# CurrentCost.net
KiCad netlist of a schematic drawn in EAGLE
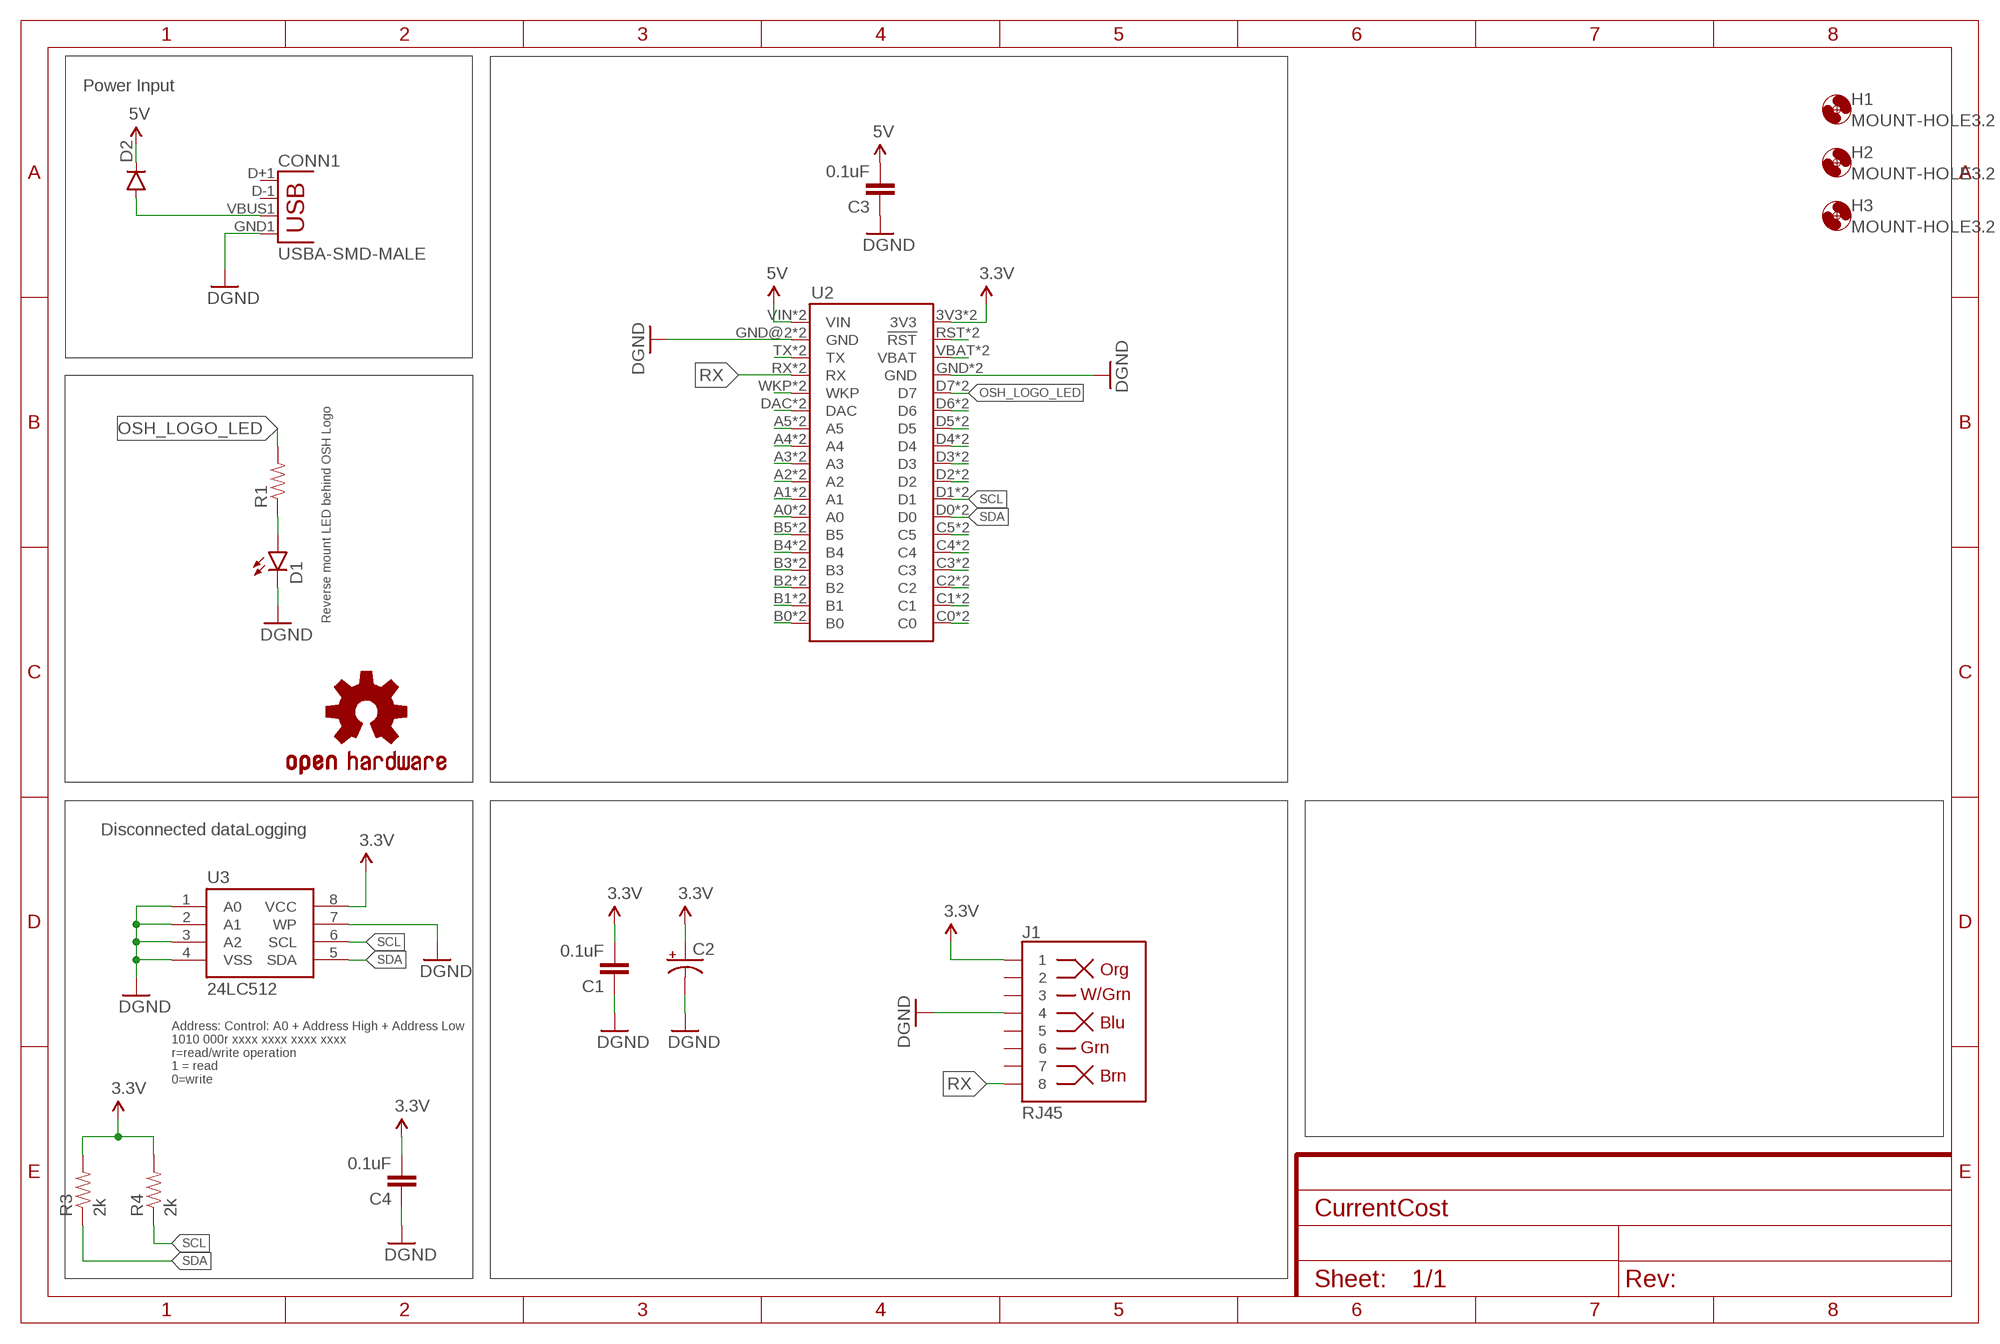
[diagram p0: schematic, sheet 1]

(export (version "E")
  (design (tool "Eeschema 10.0.6"))
  (components
    (comp (ref "C1")
      (value "0.1uF")
      (footprint "eagle-import:0805")
      (libsource (lib "eagle-import") (part "CAP0805"))
    )
    (comp (ref "C2")
      (value "CAP_POLPTH1")
      (footprint "eagle-import:CPOL-RADIAL-100UF-25V")
      (libsource (lib "eagle-import") (part "CAP_POLPTH1"))
    )
    (comp (ref "C3")
      (value "0.1uF")
      (footprint "eagle-import:0805")
      (libsource (lib "eagle-import") (part "CAP0805"))
    )
    (comp (ref "C4")
      (value "0.1uF")
      (footprint "eagle-import:0805")
      (libsource (lib "eagle-import") (part "CAP0805"))
    )
    (comp (ref "CONN1")
      (value "USBA-SMD-MALE")
      (footprint "eagle-import:USB-A-SMT-MALE")
      (libsource (lib "eagle-import") (part "USBA-SMD-MALE"))
    )
    (comp (ref "D1")
      (value "LED1206-BOTTOM")
      (footprint "eagle-import:LED-1206-BOTTOM")
      (libsource (lib "eagle-import") (part "LED1206-BOTTOM"))
    )
    (comp (ref "D2")
      (value "DIODESMA")
      (footprint "eagle-import:SMA-DIODE")
      (libsource (lib "eagle-import") (part "DIODESMA"))
    )
    (comp (ref "H1")
      (value "MOUNT-HOLE3.2")
      (footprint "eagle-import:3,2")
      (libsource (lib "eagle-import") (part "MOUNT-HOLE3.2"))
    )
    (comp (ref "H2")
      (value "MOUNT-HOLE3.2")
      (footprint "eagle-import:3,2")
      (libsource (lib "eagle-import") (part "MOUNT-HOLE3.2"))
    )
    (comp (ref "H3")
      (value "MOUNT-HOLE3.2")
      (footprint "eagle-import:3,2")
      (libsource (lib "eagle-import") (part "MOUNT-HOLE3.2"))
    )
    (comp (ref "J1")
      (value "RJ45")
      (footprint "eagle-import:RJ45-8")
      (libsource (lib "eagle-import") (part "RJ45-8PTH"))
    )
    (comp (ref "LOGO1")
      (value "OSHW-LOGOM")
      (footprint "eagle-import:OSHW-LOGO-M")
      (libsource (lib "eagle-import") (part "OSHW-LOGOM"))
    )
    (comp (ref "R1")
      (value "RESISTOR1206")
      (footprint "eagle-import:1206")
      (libsource (lib "eagle-import") (part "RESISTOR1206"))
    )
    (comp (ref "R3")
      (value "2k")
      (footprint "eagle-import:0805")
      (libsource (lib "eagle-import") (part "RESISTOR0805-RES"))
    )
    (comp (ref "R4")
      (value "2k")
      (footprint "eagle-import:0805")
      (libsource (lib "eagle-import") (part "RESISTOR0805-RES"))
    )
    (comp (ref "U2")
      (value "ELECTRONDUALNAMED")
      (footprint "eagle-import:ELECTRON_SIMPLE_SILK_NAMES_DUAL")
      (libsource (lib "eagle-import") (part "ELECTRONDUALNAMED"))
    )
    (comp (ref "U3")
      (value "24LC512")
      (footprint "eagle-import:SO08")
      (libsource (lib "eagle-import") (part "EEPROM-I2CSMD"))
    )
  )
  (nets
    (net (code "1") (name "3.3V") (class "Default")
      (node (ref "C1") (pin "2") (pinfunction "2_2") (pintype "passive"))
      (node (ref "C2") (pin "1") (pinfunction "+_1") (pintype "passive"))
      (node (ref "C4") (pin "2") (pinfunction "2_2") (pintype "passive"))
      (node (ref "J1") (pin "1") (pinfunction "1_1") (pintype "bidirectional"))
      (node (ref "R3") (pin "2") (pinfunction "2_2") (pintype "passive"))
      (node (ref "R4") (pin "2") (pinfunction "2_2") (pintype "passive"))
      (node (ref "U2") (pin "3V3") (pinfunction "3V3_3V3") (pintype "power_in"))
      (node (ref "U2") (pin "3V3_1") (pinfunction "3V3_3V3_1") (pintype "power_in"))
      (node (ref "U3") (pin "8") (pinfunction "VCC_8") (pintype "power_in"))
    )
    (net (code "2") (name "5V") (class "Default")
      (node (ref "C3") (pin "2") (pinfunction "2_2") (pintype "passive"))
      (node (ref "D2") (pin "C") (pinfunction "C_C") (pintype "passive"))
      (node (ref "U2") (pin "VIN") (pinfunction "VIN_VIN") (pintype "power_in"))
      (node (ref "U2") (pin "VIN_1B") (pinfunction "VIN_VIN_1B") (pintype "power_in"))
    )
    (net (code "3") (name "DGND") (class "Default")
      (node (ref "C1") (pin "1") (pinfunction "1_1") (pintype "passive"))
      (node (ref "C2") (pin "2") (pinfunction "-_2") (pintype "passive"))
      (node (ref "C3") (pin "1") (pinfunction "1_1") (pintype "passive"))
      (node (ref "C4") (pin "1") (pinfunction "1_1") (pintype "passive"))
      (node (ref "CONN1") (pin "GND1") (pinfunction "GND_GND1") (pintype "bidirectional"))
      (node (ref "D1") (pin "C") (pinfunction "C_C") (pintype "passive"))
      (node (ref "J1") (pin "4") (pinfunction "4_4") (pintype "bidirectional"))
      (node (ref "U2") (pin "GND") (pinfunction "GND_GND") (pintype "power_in"))
      (node (ref "U2") (pin "GND@2") (pinfunction "GND_GND@2") (pintype "power_in"))
      (node (ref "U2") (pin "GND_1") (pinfunction "GND_GND_1") (pintype "power_in"))
      (node (ref "U2") (pin "GND_1B") (pinfunction "GND_GND_1B") (pintype "power_in"))
      (node (ref "U3") (pin "1") (pinfunction "A0_1") (pintype "bidirectional"))
      (node (ref "U3") (pin "2") (pinfunction "A1_2") (pintype "bidirectional"))
      (node (ref "U3") (pin "3") (pinfunction "A2_3") (pintype "bidirectional"))
      (node (ref "U3") (pin "4") (pinfunction "VSS_4") (pintype "power_in"))
      (node (ref "U3") (pin "7") (pinfunction "WP_7") (pintype "bidirectional"))
    )
    (net (code "4") (name "Net-(CONN1-VBUS)") (class "Default")
      (node (ref "CONN1") (pin "VBUS1") (pinfunction "VBUS_VBUS1") (pintype "bidirectional"))
      (node (ref "D2") (pin "A") (pinfunction "A_A") (pintype "passive"))
    )
    (net (code "5") (name "Net-(D1-PadA)") (class "Default")
      (node (ref "D1") (pin "A") (pinfunction "A_A") (pintype "passive"))
      (node (ref "R1") (pin "1") (pinfunction "1_1") (pintype "passive"))
    )
    (net (code "6") (name "Net-(U2-A0-PadA0_1)") (class "Default")
      (node (ref "U2") (pin "A0") (pinfunction "A0_A0") (pintype "bidirectional"))
      (node (ref "U2") (pin "A0_1") (pinfunction "A0_A0_1") (pintype "bidirectional"))
    )
    (net (code "7") (name "Net-(U2-A1-PadA1_1)") (class "Default")
      (node (ref "U2") (pin "A1") (pinfunction "A1_A1") (pintype "bidirectional"))
      (node (ref "U2") (pin "A1_1") (pinfunction "A1_A1_1") (pintype "bidirectional"))
    )
    (net (code "8") (name "Net-(U2-A2-PadA2_1)") (class "Default")
      (node (ref "U2") (pin "A2") (pinfunction "A2_A2") (pintype "bidirectional"))
      (node (ref "U2") (pin "A2_1") (pinfunction "A2_A2_1") (pintype "bidirectional"))
    )
    (net (code "9") (name "Net-(U2-A3-PadA3_1)") (class "Default")
      (node (ref "U2") (pin "A3") (pinfunction "A3_A3") (pintype "bidirectional"))
      (node (ref "U2") (pin "A3_1") (pinfunction "A3_A3_1") (pintype "bidirectional"))
    )
    (net (code "10") (name "Net-(U2-A4-PadA4_1)") (class "Default")
      (node (ref "U2") (pin "A4") (pinfunction "A4_A4") (pintype "bidirectional"))
      (node (ref "U2") (pin "A4_1") (pinfunction "A4_A4_1") (pintype "bidirectional"))
    )
    (net (code "11") (name "Net-(U2-A5-PadA5_1)") (class "Default")
      (node (ref "U2") (pin "A5") (pinfunction "A5_A5") (pintype "bidirectional"))
      (node (ref "U2") (pin "A5_1") (pinfunction "A5_A5_1") (pintype "bidirectional"))
    )
    (net (code "12") (name "Net-(U2-B0-PadB0_1)") (class "Default")
      (node (ref "U2") (pin "B0") (pinfunction "B0_B0") (pintype "bidirectional"))
      (node (ref "U2") (pin "B0_1") (pinfunction "B0_B0_1") (pintype "bidirectional"))
    )
    (net (code "13") (name "Net-(U2-B1-PadB1_1)") (class "Default")
      (node (ref "U2") (pin "B1") (pinfunction "B1_B1") (pintype "bidirectional"))
      (node (ref "U2") (pin "B1_1") (pinfunction "B1_B1_1") (pintype "bidirectional"))
    )
    (net (code "14") (name "Net-(U2-B2-PadB2_1)") (class "Default")
      (node (ref "U2") (pin "B2") (pinfunction "B2_B2") (pintype "bidirectional"))
      (node (ref "U2") (pin "B2_1") (pinfunction "B2_B2_1") (pintype "bidirectional"))
    )
    (net (code "15") (name "Net-(U2-B3-PadB3_1)") (class "Default")
      (node (ref "U2") (pin "B3") (pinfunction "B3_B3") (pintype "bidirectional"))
      (node (ref "U2") (pin "B3_1") (pinfunction "B3_B3_1") (pintype "bidirectional"))
    )
    (net (code "16") (name "Net-(U2-B4-PadB4_1)") (class "Default")
      (node (ref "U2") (pin "B4") (pinfunction "B4_B4") (pintype "bidirectional"))
      (node (ref "U2") (pin "B4_1") (pinfunction "B4_B4_1") (pintype "bidirectional"))
    )
    (net (code "17") (name "Net-(U2-B5-PadB5_1)") (class "Default")
      (node (ref "U2") (pin "B5") (pinfunction "B5_B5") (pintype "bidirectional"))
      (node (ref "U2") (pin "B5_1") (pinfunction "B5_B5_1") (pintype "bidirectional"))
    )
    (net (code "18") (name "Net-(U2-C0-PadC0_1)") (class "Default")
      (node (ref "U2") (pin "C0") (pinfunction "C0_C0") (pintype "bidirectional"))
      (node (ref "U2") (pin "C0_1") (pinfunction "C0_C0_1") (pintype "bidirectional"))
    )
    (net (code "19") (name "Net-(U2-C1-PadC1_1)") (class "Default")
      (node (ref "U2") (pin "C1") (pinfunction "C1_C1") (pintype "bidirectional"))
      (node (ref "U2") (pin "C1_1") (pinfunction "C1_C1_1") (pintype "bidirectional"))
    )
    (net (code "20") (name "Net-(U2-C2-PadC2_1)") (class "Default")
      (node (ref "U2") (pin "C2") (pinfunction "C2_C2") (pintype "bidirectional"))
      (node (ref "U2") (pin "C2_1") (pinfunction "C2_C2_1") (pintype "bidirectional"))
    )
    (net (code "21") (name "Net-(U2-C3-PadC3_1)") (class "Default")
      (node (ref "U2") (pin "C3") (pinfunction "C3_C3") (pintype "bidirectional"))
      (node (ref "U2") (pin "C3_1") (pinfunction "C3_C3_1") (pintype "bidirectional"))
    )
    (net (code "22") (name "Net-(U2-C4-PadC4_1)") (class "Default")
      (node (ref "U2") (pin "C4") (pinfunction "C4_C4") (pintype "bidirectional"))
      (node (ref "U2") (pin "C4_1") (pinfunction "C4_C4_1") (pintype "bidirectional"))
    )
    (net (code "23") (name "Net-(U2-C5-PadC5_1)") (class "Default")
      (node (ref "U2") (pin "C5") (pinfunction "C5_C5") (pintype "bidirectional"))
      (node (ref "U2") (pin "C5_1") (pinfunction "C5_C5_1") (pintype "bidirectional"))
    )
    (net (code "24") (name "Net-(U2-D2-PadD2_1)") (class "Default")
      (node (ref "U2") (pin "D2") (pinfunction "D2_D2") (pintype "bidirectional"))
      (node (ref "U2") (pin "D2_1") (pinfunction "D2_D2_1") (pintype "bidirectional"))
    )
    (net (code "25") (name "Net-(U2-D3-PadD3_1)") (class "Default")
      (node (ref "U2") (pin "D3") (pinfunction "D3_D3") (pintype "bidirectional"))
      (node (ref "U2") (pin "D3_1") (pinfunction "D3_D3_1") (pintype "bidirectional"))
    )
    (net (code "26") (name "Net-(U2-D4-PadD4_1)") (class "Default")
      (node (ref "U2") (pin "D4") (pinfunction "D4_D4") (pintype "bidirectional"))
      (node (ref "U2") (pin "D4_1") (pinfunction "D4_D4_1") (pintype "bidirectional"))
    )
    (net (code "27") (name "Net-(U2-D5-PadD5_1)") (class "Default")
      (node (ref "U2") (pin "D5") (pinfunction "D5_D5") (pintype "bidirectional"))
      (node (ref "U2") (pin "D5_1") (pinfunction "D5_D5_1") (pintype "bidirectional"))
    )
    (net (code "28") (name "Net-(U2-D6-PadD6_1)") (class "Default")
      (node (ref "U2") (pin "D6") (pinfunction "D6_D6") (pintype "bidirectional"))
      (node (ref "U2") (pin "D6_1") (pinfunction "D6_D6_1") (pintype "bidirectional"))
    )
    (net (code "29") (name "Net-(U2-DAC-PadDAC_1)") (class "Default")
      (node (ref "U2") (pin "DAC") (pinfunction "DAC_DAC") (pintype "bidirectional"))
      (node (ref "U2") (pin "DAC_1") (pinfunction "DAC_DAC_1") (pintype "bidirectional"))
    )
    (net (code "30") (name "Net-(U2-PadTX)") (class "Default")
      (node (ref "U2") (pin "TX") (pinfunction "TX_TX") (pintype "bidirectional"))
      (node (ref "U2") (pin "TX_1") (pinfunction "TX_TX_1") (pintype "bidirectional"))
    )
    (net (code "31") (name "Net-(U2-PadVBAT)") (class "Default")
      (node (ref "U2") (pin "VBAT") (pinfunction "VBAT_VBAT") (pintype "passive"))
      (node (ref "U2") (pin "VBATT_1") (pinfunction "VBAT_VBATT_1") (pintype "passive"))
    )
    (net (code "32") (name "Net-(U2-PadWKP)") (class "Default")
      (node (ref "U2") (pin "WKP") (pinfunction "WKP_WKP") (pintype "bidirectional"))
      (node (ref "U2") (pin "WKP_1") (pinfunction "WKP_WKP_1") (pintype "bidirectional"))
    )
    (net (code "33") (name "Net-(U2-~{RST}-PadRST)") (class "Default")
      (node (ref "U2") (pin "RST") (pinfunction "~{RST}_RST") (pintype "bidirectional"))
      (node (ref "U2") (pin "RST_1") (pinfunction "~{RST}_RST_1") (pintype "bidirectional"))
    )
    (net (code "34") (name "OSH_LOGO_LED") (class "Default")
      (node (ref "R1") (pin "2") (pinfunction "2_2") (pintype "passive"))
      (node (ref "U2") (pin "D7") (pinfunction "D7_D7") (pintype "bidirectional"))
      (node (ref "U2") (pin "D7_1") (pinfunction "D7_D7_1") (pintype "bidirectional"))
    )
    (net (code "35") (name "RX") (class "Default")
      (node (ref "J1") (pin "8") (pinfunction "8_8") (pintype "bidirectional"))
      (node (ref "U2") (pin "RX") (pinfunction "RX_RX") (pintype "bidirectional"))
      (node (ref "U2") (pin "RX_1") (pinfunction "RX_RX_1") (pintype "bidirectional"))
    )
    (net (code "36") (name "SCL") (class "Default")
      (node (ref "R4") (pin "1") (pinfunction "1_1") (pintype "passive"))
      (node (ref "U2") (pin "D1") (pinfunction "D1_D1") (pintype "bidirectional"))
      (node (ref "U2") (pin "D1_1") (pinfunction "D1_D1_1") (pintype "bidirectional"))
      (node (ref "U3") (pin "6") (pinfunction "SCL_6") (pintype "bidirectional"))
    )
    (net (code "37") (name "SDA") (class "Default")
      (node (ref "R3") (pin "1") (pinfunction "1_1") (pintype "passive"))
      (node (ref "U2") (pin "D0") (pinfunction "D0_D0") (pintype "bidirectional"))
      (node (ref "U2") (pin "D0_1") (pinfunction "D0_D0_1") (pintype "bidirectional"))
      (node (ref "U3") (pin "5") (pinfunction "SDA_5") (pintype "bidirectional"))
    )
    (net (code "38") (name "unconnected-(CONN1-D+-PadD+1)") (class "Default")
      (node (ref "CONN1") (pin "D+1") (pinfunction "D+_D+1") (pintype "bidirectional"))
    )
    (net (code "39") (name "unconnected-(CONN1-D--PadD-1)") (class "Default")
      (node (ref "CONN1") (pin "D-1") (pinfunction "D-_D-1") (pintype "bidirectional"))
    )
    (net (code "40") (name "unconnected-(J1-Pad2)") (class "Default")
      (node (ref "J1") (pin "2") (pinfunction "2_2") (pintype "bidirectional"))
    )
    (net (code "41") (name "unconnected-(J1-Pad3)") (class "Default")
      (node (ref "J1") (pin "3") (pinfunction "3_3") (pintype "bidirectional"))
    )
    (net (code "42") (name "unconnected-(J1-Pad5)") (class "Default")
      (node (ref "J1") (pin "5") (pinfunction "5_5") (pintype "bidirectional"))
    )
    (net (code "43") (name "unconnected-(J1-Pad6)") (class "Default")
      (node (ref "J1") (pin "6") (pinfunction "6_6") (pintype "bidirectional"))
    )
    (net (code "44") (name "unconnected-(J1-Pad7)") (class "Default")
      (node (ref "J1") (pin "7") (pinfunction "7_7") (pintype "bidirectional"))
    )
  )
)
